# top_schem_rev10.net
KiCad netlist of a schematic drawn in Altium Designer
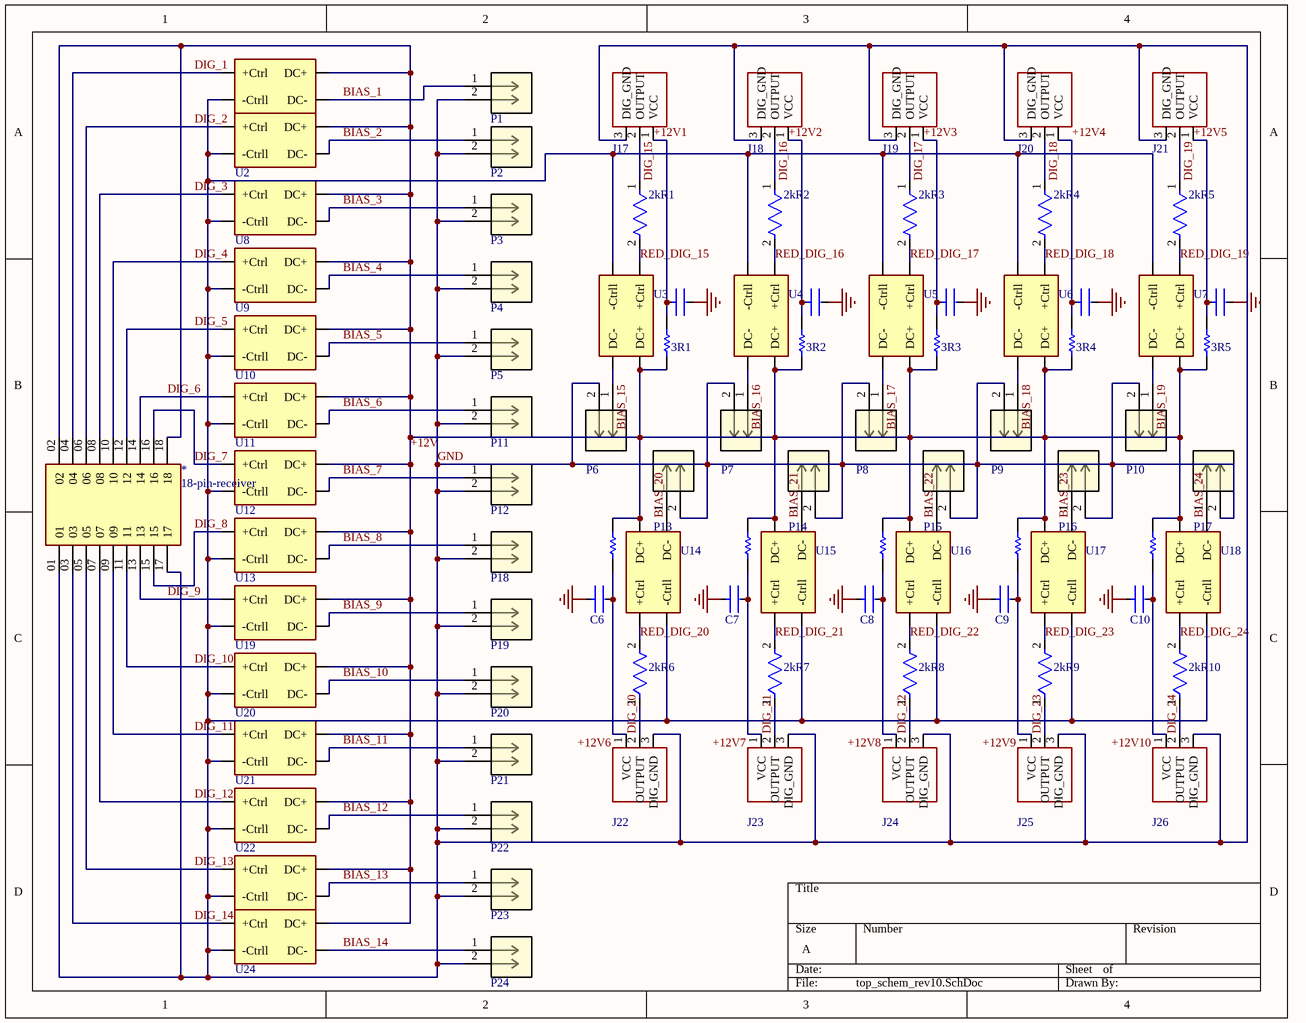
[diagram p0: top_schem_rev10.SchDoc]

(export (version "E")
  (design (tool "Eeschema 10.0.6"))
  (components
    (comp (ref "*")
      (value "18-pin-receiver")
      (footprint "18-pin-receiver")
      (libsource (lib "top_schlib") (part "18-pin-receiver"))
    )
    (comp (ref "2kR1")
      (value "CRCW06031K80FKEA")
      (footprint "2kOhm")
      (description "Res Thick Film 0603 1.8K Ohm 1% 1/10W ±100ppm/°C Molded SMD Paper T/R")
      (fields (field (name "MANUFACTURER") "Vishay") (field (name "TOLERANCE") "1%"))
      (libsource (lib "ps_schlib") (part "CRCW06031K80FKEA"))
    )
    (comp (ref "2kR2")
      (value "CRCW06031K80FKEA")
      (footprint "2kOhm")
      (description "Res Thick Film 0603 1.8K Ohm 1% 1/10W ±100ppm/°C Molded SMD Paper T/R")
      (fields (field (name "MANUFACTURER") "Vishay") (field (name "TOLERANCE") "1%"))
      (libsource (lib "ps_schlib") (part "CRCW06031K80FKEA"))
    )
    (comp (ref "2kR3")
      (value "CRCW06031K80FKEA")
      (footprint "2kOhm")
      (description "Res Thick Film 0603 1.8K Ohm 1% 1/10W ±100ppm/°C Molded SMD Paper T/R")
      (fields (field (name "MANUFACTURER") "Vishay") (field (name "TOLERANCE") "1%"))
      (libsource (lib "ps_schlib") (part "CRCW06031K80FKEA"))
    )
    (comp (ref "2kR4")
      (value "CRCW06031K80FKEA")
      (footprint "2kOhm")
      (description "Res Thick Film 0603 1.8K Ohm 1% 1/10W ±100ppm/°C Molded SMD Paper T/R")
      (fields (field (name "MANUFACTURER") "Vishay") (field (name "TOLERANCE") "1%"))
      (libsource (lib "ps_schlib") (part "CRCW06031K80FKEA"))
    )
    (comp (ref "2kR5")
      (value "CRCW06031K80FKEA")
      (footprint "2kOhm")
      (description "Res Thick Film 0603 1.8K Ohm 1% 1/10W ±100ppm/°C Molded SMD Paper T/R")
      (fields (field (name "MANUFACTURER") "Vishay") (field (name "TOLERANCE") "1%"))
      (libsource (lib "ps_schlib") (part "CRCW06031K80FKEA"))
    )
    (comp (ref "2kR6")
      (value "CRCW06031K80FKEA")
      (footprint "2kOhm")
      (description "Res Thick Film 0603 1.8K Ohm 1% 1/10W ±100ppm/°C Molded SMD Paper T/R")
      (fields (field (name "MANUFACTURER") "Vishay") (field (name "TOLERANCE") "1%"))
      (libsource (lib "ps_schlib") (part "CRCW06031K80FKEA"))
    )
    (comp (ref "2kR7")
      (value "CRCW06031K80FKEA")
      (footprint "2kOhm")
      (description "Res Thick Film 0603 1.8K Ohm 1% 1/10W ±100ppm/°C Molded SMD Paper T/R")
      (fields (field (name "MANUFACTURER") "Vishay") (field (name "TOLERANCE") "1%"))
      (libsource (lib "ps_schlib") (part "CRCW06031K80FKEA"))
    )
    (comp (ref "2kR8")
      (value "CRCW06031K80FKEA")
      (footprint "2kOhm")
      (description "Res Thick Film 0603 1.8K Ohm 1% 1/10W ±100ppm/°C Molded SMD Paper T/R")
      (fields (field (name "MANUFACTURER") "Vishay") (field (name "TOLERANCE") "1%"))
      (libsource (lib "ps_schlib") (part "CRCW06031K80FKEA"))
    )
    (comp (ref "2kR9")
      (value "CRCW06031K80FKEA")
      (footprint "2kOhm")
      (description "Res Thick Film 0603 1.8K Ohm 1% 1/10W ±100ppm/°C Molded SMD Paper T/R")
      (fields (field (name "MANUFACTURER") "Vishay") (field (name "TOLERANCE") "1%"))
      (libsource (lib "ps_schlib") (part "CRCW06031K80FKEA"))
    )
    (comp (ref "2kR10")
      (value "CRCW06031K80FKEA")
      (footprint "2kOhm")
      (description "Res Thick Film 0603 1.8K Ohm 1% 1/10W ±100ppm/°C Molded SMD Paper T/R")
      (fields (field (name "MANUFACTURER") "Vishay") (field (name "TOLERANCE") "1%"))
      (libsource (lib "ps_schlib") (part "CRCW06031K80FKEA"))
    )
    (comp (ref "3R1")
      (value "ERJ-2BQJR30X")
      (footprint "03 Ohm")
      (description "RES 0.3 OHM 5% 1/6W 0402")
      (fields (field (name "MANUFACTURER") "Panasonic") (field (name "TOLERANCE") "5%"))
      (libsource (lib "ps_schlib") (part "ERJ-2BQJR30X"))
    )
    (comp (ref "3R2")
      (value "ERJ-2BQJR30X")
      (footprint "03 Ohm")
      (description "RES 0.3 OHM 5% 1/6W 0402")
      (fields (field (name "MANUFACTURER") "Panasonic") (field (name "TOLERANCE") "5%"))
      (libsource (lib "ps_schlib") (part "ERJ-2BQJR30X"))
    )
    (comp (ref "3R3")
      (value "ERJ-2BQJR30X")
      (footprint "03 Ohm")
      (description "RES 0.3 OHM 5% 1/6W 0402")
      (fields (field (name "MANUFACTURER") "Panasonic") (field (name "TOLERANCE") "5%"))
      (libsource (lib "ps_schlib") (part "ERJ-2BQJR30X"))
    )
    (comp (ref "3R4")
      (value "ERJ-2BQJR30X")
      (footprint "03 Ohm")
      (description "RES 0.3 OHM 5% 1/6W 0402")
      (fields (field (name "MANUFACTURER") "Panasonic") (field (name "TOLERANCE") "5%"))
      (libsource (lib "ps_schlib") (part "ERJ-2BQJR30X"))
    )
    (comp (ref "3R5")
      (value "ERJ-2BQJR30X")
      (footprint "03 Ohm")
      (description "RES 0.3 OHM 5% 1/6W 0402")
      (fields (field (name "MANUFACTURER") "Panasonic") (field (name "TOLERANCE") "5%"))
      (libsource (lib "ps_schlib") (part "ERJ-2BQJR30X"))
    )
    (comp (ref "3R6")
      (value "ERJ-2BQJR30X")
      (footprint "03 Ohm")
      (description "RES 0.3 OHM 5% 1/6W 0402")
      (fields (field (name "MANUFACTURER") "Panasonic") (field (name "TOLERANCE") "5%"))
      (libsource (lib "ps_schlib") (part "ERJ-2BQJR30X"))
    )
    (comp (ref "3R7")
      (value "ERJ-2BQJR30X")
      (footprint "03 Ohm")
      (description "RES 0.3 OHM 5% 1/6W 0402")
      (fields (field (name "MANUFACTURER") "Panasonic") (field (name "TOLERANCE") "5%"))
      (libsource (lib "ps_schlib") (part "ERJ-2BQJR30X"))
    )
    (comp (ref "3R8")
      (value "ERJ-2BQJR30X")
      (footprint "03 Ohm")
      (description "RES 0.3 OHM 5% 1/6W 0402")
      (fields (field (name "MANUFACTURER") "Panasonic") (field (name "TOLERANCE") "5%"))
      (libsource (lib "ps_schlib") (part "ERJ-2BQJR30X"))
    )
    (comp (ref "3R9")
      (value "ERJ-2BQJR30X")
      (footprint "03 Ohm")
      (description "RES 0.3 OHM 5% 1/6W 0402")
      (fields (field (name "MANUFACTURER") "Panasonic") (field (name "TOLERANCE") "5%"))
      (libsource (lib "ps_schlib") (part "ERJ-2BQJR30X"))
    )
    (comp (ref "3R10")
      (value "ERJ-2BQJR30X")
      (footprint "03 Ohm")
      (description "RES 0.3 OHM 5% 1/6W 0402")
      (fields (field (name "MANUFACTURER") "Panasonic") (field (name "TOLERANCE") "5%"))
      (libsource (lib "ps_schlib") (part "ERJ-2BQJR30X"))
    )
    (comp (ref "C1")
      (value "C0805C104K5RACTU")
      (footprint "100nF")
      (description "Cap Ceramic 0.1uF 50V X7R 10% SMD 2.0 x 1.2 mm 125 C Paper T/R")
      (fields (field (name "MANUFACTURER") "KEMET") (field (name "TOLERANCE") "10%"))
      (libsource (lib "ps_schlib") (part "C0805C104K5RACTU"))
    )
    (comp (ref "C2")
      (value "C0805C104K5RACTU")
      (footprint "100nF")
      (description "Cap Ceramic 0.1uF 50V X7R 10% SMD 2.0 x 1.2 mm 125 C Paper T/R")
      (fields (field (name "MANUFACTURER") "KEMET") (field (name "TOLERANCE") "10%"))
      (libsource (lib "ps_schlib") (part "C0805C104K5RACTU"))
    )
    (comp (ref "C3")
      (value "C0805C104K5RACTU")
      (footprint "100nF")
      (description "Cap Ceramic 0.1uF 50V X7R 10% SMD 2.0 x 1.2 mm 125 C Paper T/R")
      (fields (field (name "MANUFACTURER") "KEMET") (field (name "TOLERANCE") "10%"))
      (libsource (lib "ps_schlib") (part "C0805C104K5RACTU"))
    )
    (comp (ref "C4")
      (value "C0805C104K5RACTU")
      (footprint "100nF")
      (description "Cap Ceramic 0.1uF 50V X7R 10% SMD 2.0 x 1.2 mm 125 C Paper T/R")
      (fields (field (name "MANUFACTURER") "KEMET") (field (name "TOLERANCE") "10%"))
      (libsource (lib "ps_schlib") (part "C0805C104K5RACTU"))
    )
    (comp (ref "C5")
      (value "C0805C104K5RACTU")
      (footprint "100nF")
      (description "Cap Ceramic 0.1uF 50V X7R 10% SMD 2.0 x 1.2 mm 125 C Paper T/R")
      (fields (field (name "MANUFACTURER") "KEMET") (field (name "TOLERANCE") "10%"))
      (libsource (lib "ps_schlib") (part "C0805C104K5RACTU"))
    )
    (comp (ref "C6")
      (value "C0805C104K5RACTU")
      (footprint "100nF")
      (description "Cap Ceramic 0.1uF 50V X7R 10% SMD 2.0 x 1.2 mm 125 C Paper T/R")
      (fields (field (name "MANUFACTURER") "KEMET") (field (name "TOLERANCE") "10%"))
      (libsource (lib "ps_schlib") (part "C0805C104K5RACTU"))
    )
    (comp (ref "C7")
      (value "C0805C104K5RACTU")
      (footprint "100nF")
      (description "Cap Ceramic 0.1uF 50V X7R 10% SMD 2.0 x 1.2 mm 125 C Paper T/R")
      (fields (field (name "MANUFACTURER") "KEMET") (field (name "TOLERANCE") "10%"))
      (libsource (lib "ps_schlib") (part "C0805C104K5RACTU"))
    )
    (comp (ref "C8")
      (value "C0805C104K5RACTU")
      (footprint "100nF")
      (description "Cap Ceramic 0.1uF 50V X7R 10% SMD 2.0 x 1.2 mm 125 C Paper T/R")
      (fields (field (name "MANUFACTURER") "KEMET") (field (name "TOLERANCE") "10%"))
      (libsource (lib "ps_schlib") (part "C0805C104K5RACTU"))
    )
    (comp (ref "C9")
      (value "C0805C104K5RACTU")
      (footprint "100nF")
      (description "Cap Ceramic 0.1uF 50V X7R 10% SMD 2.0 x 1.2 mm 125 C Paper T/R")
      (fields (field (name "MANUFACTURER") "KEMET") (field (name "TOLERANCE") "10%"))
      (libsource (lib "ps_schlib") (part "C0805C104K5RACTU"))
    )
    (comp (ref "C10")
      (value "C0805C104K5RACTU")
      (footprint "100nF")
      (description "Cap Ceramic 0.1uF 50V X7R 10% SMD 2.0 x 1.2 mm 125 C Paper T/R")
      (fields (field (name "MANUFACTURER") "KEMET") (field (name "TOLERANCE") "10%"))
      (libsource (lib "ps_schlib") (part "C0805C104K5RACTU"))
    )
    (comp (ref "J17")
      (value "IF-D95T")
      (footprint "IF-D95")
      (description "DETECTOR PHOTOLOGIC TTL/CMOS")
      (fields (field (name "MANUFACTURER") "Industrial Fiber Optics"))
      (libsource (lib "ps_schlib") (part "IF-D95T"))
    )
    (comp (ref "J18")
      (value "IF-D95T")
      (footprint "IF-D95")
      (description "DETECTOR PHOTOLOGIC TTL/CMOS")
      (fields (field (name "MANUFACTURER") "Industrial Fiber Optics"))
      (libsource (lib "ps_schlib") (part "IF-D95T"))
    )
    (comp (ref "J19")
      (value "IF-D95T")
      (footprint "IF-D95")
      (description "DETECTOR PHOTOLOGIC TTL/CMOS")
      (fields (field (name "MANUFACTURER") "Industrial Fiber Optics"))
      (libsource (lib "ps_schlib") (part "IF-D95T"))
    )
    (comp (ref "J20")
      (value "IF-D95T")
      (footprint "IF-D95")
      (description "DETECTOR PHOTOLOGIC TTL/CMOS")
      (fields (field (name "MANUFACTURER") "Industrial Fiber Optics"))
      (libsource (lib "ps_schlib") (part "IF-D95T"))
    )
    (comp (ref "J21")
      (value "IF-D95T")
      (footprint "IF-D95")
      (description "DETECTOR PHOTOLOGIC TTL/CMOS")
      (fields (field (name "MANUFACTURER") "Industrial Fiber Optics"))
      (libsource (lib "ps_schlib") (part "IF-D95T"))
    )
    (comp (ref "J22")
      (value "IF-D95T")
      (footprint "IF-D95")
      (description "DETECTOR PHOTOLOGIC TTL/CMOS")
      (fields (field (name "MANUFACTURER") "Industrial Fiber Optics"))
      (libsource (lib "ps_schlib") (part "IF-D95T"))
    )
    (comp (ref "J23")
      (value "IF-D95T")
      (footprint "IF-D95")
      (description "DETECTOR PHOTOLOGIC TTL/CMOS")
      (fields (field (name "MANUFACTURER") "Industrial Fiber Optics"))
      (libsource (lib "ps_schlib") (part "IF-D95T"))
    )
    (comp (ref "J24")
      (value "IF-D95T")
      (footprint "IF-D95")
      (description "DETECTOR PHOTOLOGIC TTL/CMOS")
      (fields (field (name "MANUFACTURER") "Industrial Fiber Optics"))
      (libsource (lib "ps_schlib") (part "IF-D95T"))
    )
    (comp (ref "J25")
      (value "IF-D95T")
      (footprint "IF-D95")
      (description "DETECTOR PHOTOLOGIC TTL/CMOS")
      (fields (field (name "MANUFACTURER") "Industrial Fiber Optics"))
      (libsource (lib "ps_schlib") (part "IF-D95T"))
    )
    (comp (ref "J26")
      (value "IF-D95T")
      (footprint "IF-D95")
      (description "DETECTOR PHOTOLOGIC TTL/CMOS")
      (fields (field (name "MANUFACTURER") "Industrial Fiber Optics"))
      (libsource (lib "ps_schlib") (part "IF-D95T"))
    )
    (comp (ref "P1")
      (value "1054311102")
      (footprint "CONN_1054311102_MOL")
      (fields (field (name "MANUFACTURER") "Molex"))
      (libsource (lib "ps_schlib") (part "1054311102"))
    )
    (comp (ref "P2")
      (value "1054311102")
      (footprint "CONN_1054311102_MOL")
      (fields (field (name "MANUFACTURER") "Molex"))
      (libsource (lib "ps_schlib") (part "1054311102"))
    )
    (comp (ref "P3")
      (value "1054311102")
      (footprint "CONN_1054311102_MOL")
      (fields (field (name "MANUFACTURER") "Molex"))
      (libsource (lib "ps_schlib") (part "1054311102"))
    )
    (comp (ref "P4")
      (value "1054311102")
      (footprint "CONN_1054311102_MOL")
      (fields (field (name "MANUFACTURER") "Molex"))
      (libsource (lib "ps_schlib") (part "1054311102"))
    )
    (comp (ref "P5")
      (value "1054311102")
      (footprint "CONN_1054311102_MOL")
      (fields (field (name "MANUFACTURER") "Molex"))
      (libsource (lib "ps_schlib") (part "1054311102"))
    )
    (comp (ref "P6")
      (value "1054311102")
      (footprint "CONN_1054311102_MOL")
      (fields (field (name "MANUFACTURER") "Molex"))
      (libsource (lib "") (part "1054311102_2"))
    )
    (comp (ref "P7")
      (value "1054311102")
      (footprint "CONN_1054311102_MOL")
      (fields (field (name "MANUFACTURER") "Molex"))
      (libsource (lib "") (part "1054311102_2"))
    )
    (comp (ref "P8")
      (value "1054311102")
      (footprint "CONN_1054311102_MOL")
      (fields (field (name "MANUFACTURER") "Molex"))
      (libsource (lib "") (part "1054311102_2"))
    )
    (comp (ref "P9")
      (value "1054311102")
      (footprint "CONN_1054311102_MOL")
      (fields (field (name "MANUFACTURER") "Molex"))
      (libsource (lib "") (part "1054311102_2"))
    )
    (comp (ref "P10")
      (value "1054311102")
      (footprint "CONN_1054311102_MOL")
      (fields (field (name "MANUFACTURER") "Molex"))
      (libsource (lib "") (part "1054311102_2"))
    )
    (comp (ref "P11")
      (value "1054311102")
      (footprint "CONN_1054311102_MOL")
      (fields (field (name "MANUFACTURER") "Molex"))
      (libsource (lib "ps_schlib") (part "1054311102"))
    )
    (comp (ref "P12")
      (value "1054311102")
      (footprint "CONN_1054311102_MOL")
      (fields (field (name "MANUFACTURER") "Molex"))
      (libsource (lib "ps_schlib") (part "1054311102"))
    )
    (comp (ref "P13")
      (value "1054311102")
      (footprint "CONN_1054311102_MOL")
      (fields (field (name "MANUFACTURER") "Molex"))
      (libsource (lib "") (part "1054311102_1"))
    )
    (comp (ref "P14")
      (value "1054311102")
      (footprint "CONN_1054311102_MOL")
      (fields (field (name "MANUFACTURER") "Molex"))
      (libsource (lib "") (part "1054311102_1"))
    )
    (comp (ref "P15")
      (value "1054311102")
      (footprint "CONN_1054311102_MOL")
      (fields (field (name "MANUFACTURER") "Molex"))
      (libsource (lib "") (part "1054311102_1"))
    )
    (comp (ref "P16")
      (value "1054311102")
      (footprint "CONN_1054311102_MOL")
      (fields (field (name "MANUFACTURER") "Molex"))
      (libsource (lib "") (part "1054311102_1"))
    )
    (comp (ref "P17")
      (value "1054311102")
      (footprint "CONN_1054311102_MOL")
      (fields (field (name "MANUFACTURER") "Molex"))
      (libsource (lib "") (part "1054311102_1"))
    )
    (comp (ref "P18")
      (value "1054311102")
      (footprint "CONN_1054311102_MOL")
      (fields (field (name "MANUFACTURER") "Molex"))
      (libsource (lib "ps_schlib") (part "1054311102"))
    )
    (comp (ref "P19")
      (value "1054311102")
      (footprint "CONN_1054311102_MOL")
      (fields (field (name "MANUFACTURER") "Molex"))
      (libsource (lib "ps_schlib") (part "1054311102"))
    )
    (comp (ref "P20")
      (value "1054311102")
      (footprint "CONN_1054311102_MOL")
      (fields (field (name "MANUFACTURER") "Molex"))
      (libsource (lib "ps_schlib") (part "1054311102"))
    )
    (comp (ref "P21")
      (value "1054311102")
      (footprint "CONN_1054311102_MOL")
      (fields (field (name "MANUFACTURER") "Molex"))
      (libsource (lib "ps_schlib") (part "1054311102"))
    )
    (comp (ref "P22")
      (value "1054311102")
      (footprint "CONN_1054311102_MOL")
      (fields (field (name "MANUFACTURER") "Molex"))
      (libsource (lib "ps_schlib") (part "1054311102"))
    )
    (comp (ref "P23")
      (value "1054311102")
      (footprint "CONN_1054311102_MOL")
      (fields (field (name "MANUFACTURER") "Molex"))
      (libsource (lib "ps_schlib") (part "1054311102"))
    )
    (comp (ref "P24")
      (value "1054311102")
      (footprint "CONN_1054311102_MOL")
      (fields (field (name "MANUFACTURER") "Molex"))
      (libsource (lib "ps_schlib") (part "1054311102"))
    )
    (comp (ref "U1")
      (value "Solid state relay")
      (footprint "CPC1002N")
      (libsource (lib "ps_schlib") (part "CPC1002N"))
    )
    (comp (ref "U2")
      (value "Solid state relay")
      (footprint "CPC1002N")
      (libsource (lib "ps_schlib") (part "CPC1002N"))
    )
    (comp (ref "U3")
      (value "Solid state relay")
      (footprint "CPC1002N")
      (libsource (lib "") (part "CPC1002N_1"))
    )
    (comp (ref "U4")
      (value "Solid state relay")
      (footprint "CPC1002N")
      (libsource (lib "") (part "CPC1002N_1"))
    )
    (comp (ref "U5")
      (value "Solid state relay")
      (footprint "CPC1002N")
      (libsource (lib "") (part "CPC1002N_1"))
    )
    (comp (ref "U6")
      (value "Solid state relay")
      (footprint "CPC1002N")
      (libsource (lib "") (part "CPC1002N_1"))
    )
    (comp (ref "U7")
      (value "Solid state relay")
      (footprint "CPC1002N")
      (libsource (lib "") (part "CPC1002N_1"))
    )
    (comp (ref "U8")
      (value "Solid state relay")
      (footprint "CPC1002N")
      (libsource (lib "ps_schlib") (part "CPC1002N"))
    )
    (comp (ref "U9")
      (value "Solid state relay")
      (footprint "CPC1002N")
      (libsource (lib "ps_schlib") (part "CPC1002N"))
    )
    (comp (ref "U10")
      (value "Solid state relay")
      (footprint "CPC1002N")
      (libsource (lib "ps_schlib") (part "CPC1002N"))
    )
    (comp (ref "U11")
      (value "Solid state relay")
      (footprint "CPC1002N")
      (libsource (lib "ps_schlib") (part "CPC1002N"))
    )
    (comp (ref "U12")
      (value "Solid state relay")
      (footprint "CPC1002N")
      (libsource (lib "ps_schlib") (part "CPC1002N"))
    )
    (comp (ref "U13")
      (value "Solid state relay")
      (footprint "CPC1002N")
      (libsource (lib "ps_schlib") (part "CPC1002N"))
    )
    (comp (ref "U14")
      (value "Solid state relay")
      (footprint "CPC1002N")
      (libsource (lib "") (part "CPC1002N_2"))
    )
    (comp (ref "U15")
      (value "Solid state relay")
      (footprint "CPC1002N")
      (libsource (lib "") (part "CPC1002N_2"))
    )
    (comp (ref "U16")
      (value "Solid state relay")
      (footprint "CPC1002N")
      (libsource (lib "") (part "CPC1002N_2"))
    )
    (comp (ref "U17")
      (value "Solid state relay")
      (footprint "CPC1002N")
      (libsource (lib "") (part "CPC1002N_2"))
    )
    (comp (ref "U18")
      (value "Solid state relay")
      (footprint "CPC1002N")
      (libsource (lib "") (part "CPC1002N_2"))
    )
    (comp (ref "U19")
      (value "Solid state relay")
      (footprint "CPC1002N")
      (libsource (lib "ps_schlib") (part "CPC1002N"))
    )
    (comp (ref "U20")
      (value "Solid state relay")
      (footprint "CPC1002N")
      (libsource (lib "ps_schlib") (part "CPC1002N"))
    )
    (comp (ref "U21")
      (value "Solid state relay")
      (footprint "CPC1002N")
      (libsource (lib "ps_schlib") (part "CPC1002N"))
    )
    (comp (ref "U22")
      (value "Solid state relay")
      (footprint "CPC1002N")
      (libsource (lib "ps_schlib") (part "CPC1002N"))
    )
    (comp (ref "U23")
      (value "Solid state relay")
      (footprint "CPC1002N")
      (libsource (lib "ps_schlib") (part "CPC1002N"))
    )
    (comp (ref "U24")
      (value "Solid state relay")
      (footprint "CPC1002N")
      (libsource (lib "ps_schlib") (part "CPC1002N"))
    )
  )
  (nets
    (net (code "1") (name "/+12V") (class "Default")
      (node (ref "*") (pin "02") (pinfunction "02_02") (pintype "passive"))
      (node (ref "*") (pin "18") (pinfunction "18_18") (pintype "passive"))
      (node (ref "3R1") (pin "1") (pinfunction "1_1") (pintype "passive"))
      (node (ref "3R10") (pin "2") (pinfunction "2_2") (pintype "passive"))
      (node (ref "3R2") (pin "1") (pinfunction "1_1") (pintype "passive"))
      (node (ref "3R3") (pin "1") (pinfunction "1_1") (pintype "passive"))
      (node (ref "3R4") (pin "1") (pinfunction "1_1") (pintype "passive"))
      (node (ref "3R5") (pin "1") (pinfunction "1_1") (pintype "passive"))
      (node (ref "3R6") (pin "2") (pinfunction "2_2") (pintype "passive"))
      (node (ref "3R7") (pin "2") (pinfunction "2_2") (pintype "passive"))
      (node (ref "3R8") (pin "2") (pinfunction "2_2") (pintype "passive"))
      (node (ref "3R9") (pin "2") (pinfunction "2_2") (pintype "passive"))
      (node (ref "U1") (pin "4") (pinfunction "DC+_4") (pintype "passive"))
      (node (ref "U10") (pin "4") (pinfunction "DC+_4") (pintype "passive"))
      (node (ref "U11") (pin "4") (pinfunction "DC+_4") (pintype "passive"))
      (node (ref "U12") (pin "4") (pinfunction "DC+_4") (pintype "passive"))
      (node (ref "U13") (pin "4") (pinfunction "DC+_4") (pintype "passive"))
      (node (ref "U14") (pin "4") (pinfunction "DC+_4") (pintype "passive"))
      (node (ref "U15") (pin "4") (pinfunction "DC+_4") (pintype "passive"))
      (node (ref "U16") (pin "4") (pinfunction "DC+_4") (pintype "passive"))
      (node (ref "U17") (pin "4") (pinfunction "DC+_4") (pintype "passive"))
      (node (ref "U18") (pin "4") (pinfunction "DC+_4") (pintype "passive"))
      (node (ref "U19") (pin "4") (pinfunction "DC+_4") (pintype "passive"))
      (node (ref "U2") (pin "4") (pinfunction "DC+_4") (pintype "passive"))
      (node (ref "U20") (pin "4") (pinfunction "DC+_4") (pintype "passive"))
      (node (ref "U21") (pin "4") (pinfunction "DC+_4") (pintype "passive"))
      (node (ref "U22") (pin "4") (pinfunction "DC+_4") (pintype "passive"))
      (node (ref "U23") (pin "4") (pinfunction "DC+_4") (pintype "passive"))
      (node (ref "U24") (pin "4") (pinfunction "DC+_4") (pintype "passive"))
      (node (ref "U3") (pin "4") (pinfunction "DC+_4") (pintype "passive"))
      (node (ref "U4") (pin "4") (pinfunction "DC+_4") (pintype "passive"))
      (node (ref "U5") (pin "4") (pinfunction "DC+_4") (pintype "passive"))
      (node (ref "U6") (pin "4") (pinfunction "DC+_4") (pintype "passive"))
      (node (ref "U7") (pin "4") (pinfunction "DC+_4") (pintype "passive"))
      (node (ref "U8") (pin "4") (pinfunction "DC+_4") (pintype "passive"))
      (node (ref "U9") (pin "4") (pinfunction "DC+_4") (pintype "passive"))
    )
    (net (code "2") (name "/+12V1") (class "Default")
      (node (ref "3R1") (pin "2") (pinfunction "2_2") (pintype "passive"))
      (node (ref "C1") (pin "1") (pinfunction "1_1") (pintype "passive"))
      (node (ref "J17") (pin "1") (pinfunction "VCC_1") (pintype "passive"))
    )
    (net (code "3") (name "/+12V2") (class "Default")
      (node (ref "3R2") (pin "2") (pinfunction "2_2") (pintype "passive"))
      (node (ref "C2") (pin "1") (pinfunction "1_1") (pintype "passive"))
      (node (ref "J18") (pin "1") (pinfunction "VCC_1") (pintype "passive"))
    )
    (net (code "4") (name "/+12V3") (class "Default")
      (node (ref "3R3") (pin "2") (pinfunction "2_2") (pintype "passive"))
      (node (ref "C3") (pin "1") (pinfunction "1_1") (pintype "passive"))
      (node (ref "J19") (pin "1") (pinfunction "VCC_1") (pintype "passive"))
    )
    (net (code "5") (name "/+12V4") (class "Default")
      (node (ref "3R4") (pin "2") (pinfunction "2_2") (pintype "passive"))
      (node (ref "C4") (pin "1") (pinfunction "1_1") (pintype "passive"))
      (node (ref "J20") (pin "1") (pinfunction "VCC_1") (pintype "passive"))
    )
    (net (code "6") (name "/+12V5") (class "Default")
      (node (ref "3R5") (pin "2") (pinfunction "2_2") (pintype "passive"))
      (node (ref "C5") (pin "1") (pinfunction "1_1") (pintype "passive"))
      (node (ref "J21") (pin "1") (pinfunction "VCC_1") (pintype "passive"))
    )
    (net (code "7") (name "/+12V6") (class "Default")
      (node (ref "3R6") (pin "1") (pinfunction "1_1") (pintype "passive"))
      (node (ref "C6") (pin "2") (pinfunction "2_2") (pintype "passive"))
      (node (ref "J22") (pin "1") (pinfunction "VCC_1") (pintype "passive"))
    )
    (net (code "8") (name "/+12V7") (class "Default")
      (node (ref "3R7") (pin "1") (pinfunction "1_1") (pintype "passive"))
      (node (ref "C7") (pin "2") (pinfunction "2_2") (pintype "passive"))
      (node (ref "J23") (pin "1") (pinfunction "VCC_1") (pintype "passive"))
    )
    (net (code "9") (name "/+12V8") (class "Default")
      (node (ref "3R8") (pin "1") (pinfunction "1_1") (pintype "passive"))
      (node (ref "C8") (pin "2") (pinfunction "2_2") (pintype "passive"))
      (node (ref "J24") (pin "1") (pinfunction "VCC_1") (pintype "passive"))
    )
    (net (code "10") (name "/+12V9") (class "Default")
      (node (ref "3R9") (pin "1") (pinfunction "1_1") (pintype "passive"))
      (node (ref "C9") (pin "2") (pinfunction "2_2") (pintype "passive"))
      (node (ref "J25") (pin "1") (pinfunction "VCC_1") (pintype "passive"))
    )
    (net (code "11") (name "/+12V10") (class "Default")
      (node (ref "3R10") (pin "1") (pinfunction "1_1") (pintype "passive"))
      (node (ref "C10") (pin "2") (pinfunction "2_2") (pintype "passive"))
      (node (ref "J26") (pin "1") (pinfunction "VCC_1") (pintype "passive"))
    )
    (net (code "12") (name "/BIAS_1") (class "Default")
      (node (ref "P1") (pin "1") (pinfunction "1_1") (pintype "passive"))
      (node (ref "U1") (pin "3") (pinfunction "DC-_3") (pintype "passive"))
    )
    (net (code "13") (name "/BIAS_2") (class "Default")
      (node (ref "P2") (pin "1") (pinfunction "1_1") (pintype "passive"))
      (node (ref "U2") (pin "3") (pinfunction "DC-_3") (pintype "passive"))
    )
    (net (code "14") (name "/BIAS_3") (class "Default")
      (node (ref "P3") (pin "1") (pinfunction "1_1") (pintype "passive"))
      (node (ref "U8") (pin "3") (pinfunction "DC-_3") (pintype "passive"))
    )
    (net (code "15") (name "/BIAS_4") (class "Default")
      (node (ref "P4") (pin "1") (pinfunction "1_1") (pintype "passive"))
      (node (ref "U9") (pin "3") (pinfunction "DC-_3") (pintype "passive"))
    )
    (net (code "16") (name "/BIAS_5") (class "Default")
      (node (ref "P5") (pin "1") (pinfunction "1_1") (pintype "passive"))
      (node (ref "U10") (pin "3") (pinfunction "DC-_3") (pintype "passive"))
    )
    (net (code "17") (name "/BIAS_6") (class "Default")
      (node (ref "P11") (pin "1") (pinfunction "1_1") (pintype "passive"))
      (node (ref "U11") (pin "3") (pinfunction "DC-_3") (pintype "passive"))
    )
    (net (code "18") (name "/BIAS_7") (class "Default")
      (node (ref "P12") (pin "1") (pinfunction "1_1") (pintype "passive"))
      (node (ref "U12") (pin "3") (pinfunction "DC-_3") (pintype "passive"))
    )
    (net (code "19") (name "/BIAS_8") (class "Default")
      (node (ref "P18") (pin "1") (pinfunction "1_1") (pintype "passive"))
      (node (ref "U13") (pin "3") (pinfunction "DC-_3") (pintype "passive"))
    )
    (net (code "20") (name "/BIAS_9") (class "Default")
      (node (ref "P19") (pin "1") (pinfunction "1_1") (pintype "passive"))
      (node (ref "U19") (pin "3") (pinfunction "DC-_3") (pintype "passive"))
    )
    (net (code "21") (name "/BIAS_10") (class "Default")
      (node (ref "P20") (pin "1") (pinfunction "1_1") (pintype "passive"))
      (node (ref "U20") (pin "3") (pinfunction "DC-_3") (pintype "passive"))
    )
    (net (code "22") (name "/BIAS_11") (class "Default")
      (node (ref "P21") (pin "1") (pinfunction "1_1") (pintype "passive"))
      (node (ref "U21") (pin "3") (pinfunction "DC-_3") (pintype "passive"))
    )
    (net (code "23") (name "/BIAS_12") (class "Default")
      (node (ref "P22") (pin "1") (pinfunction "1_1") (pintype "passive"))
      (node (ref "U22") (pin "3") (pinfunction "DC-_3") (pintype "passive"))
    )
    (net (code "24") (name "/BIAS_13") (class "Default")
      (node (ref "P23") (pin "1") (pinfunction "1_1") (pintype "passive"))
      (node (ref "U23") (pin "3") (pinfunction "DC-_3") (pintype "passive"))
    )
    (net (code "25") (name "/BIAS_14") (class "Default")
      (node (ref "P24") (pin "1") (pinfunction "1_1") (pintype "passive"))
      (node (ref "U24") (pin "3") (pinfunction "DC-_3") (pintype "passive"))
    )
    (net (code "26") (name "/BIAS_15") (class "Default")
      (node (ref "P6") (pin "1") (pinfunction "1_1") (pintype "passive"))
      (node (ref "U3") (pin "3") (pinfunction "DC-_3") (pintype "passive"))
    )
    (net (code "27") (name "/BIAS_16") (class "Default")
      (node (ref "P7") (pin "1") (pinfunction "1_1") (pintype "passive"))
      (node (ref "U4") (pin "3") (pinfunction "DC-_3") (pintype "passive"))
    )
    (net (code "28") (name "/BIAS_17") (class "Default")
      (node (ref "P8") (pin "1") (pinfunction "1_1") (pintype "passive"))
      (node (ref "U5") (pin "3") (pinfunction "DC-_3") (pintype "passive"))
    )
    (net (code "29") (name "/BIAS_18") (class "Default")
      (node (ref "P9") (pin "1") (pinfunction "1_1") (pintype "passive"))
      (node (ref "U6") (pin "3") (pinfunction "DC-_3") (pintype "passive"))
    )
    (net (code "30") (name "/BIAS_19") (class "Default")
      (node (ref "P10") (pin "1") (pinfunction "1_1") (pintype "passive"))
      (node (ref "U7") (pin "3") (pinfunction "DC-_3") (pintype "passive"))
    )
    (net (code "31") (name "/BIAS_20") (class "Default")
      (node (ref "P13") (pin "1") (pinfunction "1_1") (pintype "passive"))
      (node (ref "U14") (pin "3") (pinfunction "DC-_3") (pintype "passive"))
    )
    (net (code "32") (name "/BIAS_21") (class "Default")
      (node (ref "P14") (pin "1") (pinfunction "1_1") (pintype "passive"))
      (node (ref "U15") (pin "3") (pinfunction "DC-_3") (pintype "passive"))
    )
    (net (code "33") (name "/BIAS_22") (class "Default")
      (node (ref "P15") (pin "1") (pinfunction "1_1") (pintype "passive"))
      (node (ref "U16") (pin "3") (pinfunction "DC-_3") (pintype "passive"))
    )
    (net (code "34") (name "/BIAS_23") (class "Default")
      (node (ref "P16") (pin "1") (pinfunction "1_1") (pintype "passive"))
      (node (ref "U17") (pin "3") (pinfunction "DC-_3") (pintype "passive"))
    )
    (net (code "35") (name "/BIAS_24") (class "Default")
      (node (ref "P17") (pin "1") (pinfunction "1_1") (pintype "passive"))
      (node (ref "U18") (pin "3") (pinfunction "DC-_3") (pintype "passive"))
    )
    (net (code "36") (name "/DIG_1") (class "Default")
      (node (ref "*") (pin "04") (pinfunction "04_04") (pintype "passive"))
      (node (ref "U1") (pin "1") (pinfunction "+Ctrl_1") (pintype "passive"))
    )
    (net (code "37") (name "/DIG_2") (class "Default")
      (node (ref "*") (pin "06") (pinfunction "06_06") (pintype "passive"))
      (node (ref "U2") (pin "1") (pinfunction "+Ctrl_1") (pintype "passive"))
    )
    (net (code "38") (name "/DIG_3") (class "Default")
      (node (ref "*") (pin "08") (pinfunction "08_08") (pintype "passive"))
      (node (ref "U8") (pin "1") (pinfunction "+Ctrl_1") (pintype "passive"))
    )
    (net (code "39") (name "/DIG_4") (class "Default")
      (node (ref "*") (pin "10") (pinfunction "10_10") (pintype "passive"))
      (node (ref "U9") (pin "1") (pinfunction "+Ctrl_1") (pintype "passive"))
    )
    (net (code "40") (name "/DIG_5") (class "Default")
      (node (ref "*") (pin "12") (pinfunction "12_12") (pintype "passive"))
      (node (ref "U10") (pin "1") (pinfunction "+Ctrl_1") (pintype "passive"))
    )
    (net (code "41") (name "/DIG_6") (class "Default")
      (node (ref "*") (pin "14") (pinfunction "14_14") (pintype "passive"))
      (node (ref "U11") (pin "1") (pinfunction "+Ctrl_1") (pintype "passive"))
    )
    (net (code "42") (name "/DIG_7") (class "Default")
      (node (ref "*") (pin "16") (pinfunction "16_16") (pintype "passive"))
      (node (ref "U12") (pin "1") (pinfunction "+Ctrl_1") (pintype "passive"))
    )
    (net (code "43") (name "/DIG_8") (class "Default")
      (node (ref "*") (pin "15") (pinfunction "15_15") (pintype "passive"))
      (node (ref "U13") (pin "1") (pinfunction "+Ctrl_1") (pintype "passive"))
    )
    (net (code "44") (name "/DIG_9") (class "Default")
      (node (ref "*") (pin "13") (pinfunction "13_13") (pintype "passive"))
      (node (ref "U19") (pin "1") (pinfunction "+Ctrl_1") (pintype "passive"))
    )
    (net (code "45") (name "/DIG_10") (class "Default")
      (node (ref "*") (pin "11") (pinfunction "11_11") (pintype "passive"))
      (node (ref "U20") (pin "1") (pinfunction "+Ctrl_1") (pintype "passive"))
    )
    (net (code "46") (name "/DIG_11") (class "Default")
      (node (ref "*") (pin "09") (pinfunction "09_09") (pintype "passive"))
      (node (ref "U21") (pin "1") (pinfunction "+Ctrl_1") (pintype "passive"))
    )
    (net (code "47") (name "/DIG_12") (class "Default")
      (node (ref "*") (pin "07") (pinfunction "07_07") (pintype "passive"))
      (node (ref "U22") (pin "1") (pinfunction "+Ctrl_1") (pintype "passive"))
    )
    (net (code "48") (name "/DIG_13") (class "Default")
      (node (ref "*") (pin "05") (pinfunction "05_05") (pintype "passive"))
      (node (ref "U23") (pin "1") (pinfunction "+Ctrl_1") (pintype "passive"))
    )
    (net (code "49") (name "/DIG_14") (class "Default")
      (node (ref "*") (pin "03") (pinfunction "03_03") (pintype "passive"))
      (node (ref "U24") (pin "1") (pinfunction "+Ctrl_1") (pintype "passive"))
    )
    (net (code "50") (name "/DIG_15") (class "Default")
      (node (ref "2kR1") (pin "1") (pinfunction "1_1") (pintype "passive"))
      (node (ref "J17") (pin "2") (pinfunction "OUTPUT_2") (pintype "passive"))
    )
    (net (code "51") (name "/DIG_16") (class "Default")
      (node (ref "2kR2") (pin "1") (pinfunction "1_1") (pintype "passive"))
      (node (ref "J18") (pin "2") (pinfunction "OUTPUT_2") (pintype "passive"))
    )
    (net (code "52") (name "/DIG_17") (class "Default")
      (node (ref "2kR3") (pin "1") (pinfunction "1_1") (pintype "passive"))
      (node (ref "J19") (pin "2") (pinfunction "OUTPUT_2") (pintype "passive"))
    )
    (net (code "53") (name "/DIG_18") (class "Default")
      (node (ref "2kR4") (pin "1") (pinfunction "1_1") (pintype "passive"))
      (node (ref "J20") (pin "2") (pinfunction "OUTPUT_2") (pintype "passive"))
    )
    (net (code "54") (name "/DIG_19") (class "Default")
      (node (ref "2kR5") (pin "1") (pinfunction "1_1") (pintype "passive"))
      (node (ref "J21") (pin "2") (pinfunction "OUTPUT_2") (pintype "passive"))
    )
    (net (code "55") (name "/DIG_20") (class "Default")
      (node (ref "2kR6") (pin "1") (pinfunction "1_1") (pintype "passive"))
      (node (ref "J22") (pin "2") (pinfunction "OUTPUT_2") (pintype "passive"))
    )
    (net (code "56") (name "/DIG_21") (class "Default")
      (node (ref "2kR7") (pin "1") (pinfunction "1_1") (pintype "passive"))
      (node (ref "J23") (pin "2") (pinfunction "OUTPUT_2") (pintype "passive"))
    )
    (net (code "57") (name "/DIG_22") (class "Default")
      (node (ref "2kR8") (pin "1") (pinfunction "1_1") (pintype "passive"))
      (node (ref "J24") (pin "2") (pinfunction "OUTPUT_2") (pintype "passive"))
    )
    (net (code "58") (name "/DIG_23") (class "Default")
      (node (ref "2kR9") (pin "1") (pinfunction "1_1") (pintype "passive"))
      (node (ref "J25") (pin "2") (pinfunction "OUTPUT_2") (pintype "passive"))
    )
    (net (code "59") (name "/DIG_24") (class "Default")
      (node (ref "2kR10") (pin "1") (pinfunction "1_1") (pintype "passive"))
      (node (ref "J26") (pin "2") (pinfunction "OUTPUT_2") (pintype "passive"))
    )
    (net (code "60") (name "/RED_DIG_15") (class "Default")
      (node (ref "2kR1") (pin "2") (pinfunction "2_2") (pintype "passive"))
      (node (ref "U3") (pin "1") (pinfunction "+Ctrl_1") (pintype "passive"))
    )
    (net (code "61") (name "/RED_DIG_16") (class "Default")
      (node (ref "2kR2") (pin "2") (pinfunction "2_2") (pintype "passive"))
      (node (ref "U4") (pin "1") (pinfunction "+Ctrl_1") (pintype "passive"))
    )
    (net (code "62") (name "/RED_DIG_17") (class "Default")
      (node (ref "2kR3") (pin "2") (pinfunction "2_2") (pintype "passive"))
      (node (ref "U5") (pin "1") (pinfunction "+Ctrl_1") (pintype "passive"))
    )
    (net (code "63") (name "/RED_DIG_18") (class "Default")
      (node (ref "2kR4") (pin "2") (pinfunction "2_2") (pintype "passive"))
      (node (ref "U6") (pin "1") (pinfunction "+Ctrl_1") (pintype "passive"))
    )
    (net (code "64") (name "/RED_DIG_19") (class "Default")
      (node (ref "2kR5") (pin "2") (pinfunction "2_2") (pintype "passive"))
      (node (ref "U7") (pin "1") (pinfunction "+Ctrl_1") (pintype "passive"))
    )
    (net (code "65") (name "/RED_DIG_20") (class "Default")
      (node (ref "2kR6") (pin "2") (pinfunction "2_2") (pintype "passive"))
      (node (ref "U14") (pin "1") (pinfunction "+Ctrl_1") (pintype "passive"))
    )
    (net (code "66") (name "/RED_DIG_21") (class "Default")
      (node (ref "2kR7") (pin "2") (pinfunction "2_2") (pintype "passive"))
      (node (ref "U15") (pin "1") (pinfunction "+Ctrl_1") (pintype "passive"))
    )
    (net (code "67") (name "/RED_DIG_22") (class "Default")
      (node (ref "2kR8") (pin "2") (pinfunction "2_2") (pintype "passive"))
      (node (ref "U16") (pin "1") (pinfunction "+Ctrl_1") (pintype "passive"))
    )
    (net (code "68") (name "/RED_DIG_23") (class "Default")
      (node (ref "2kR9") (pin "2") (pinfunction "2_2") (pintype "passive"))
      (node (ref "U17") (pin "1") (pinfunction "+Ctrl_1") (pintype "passive"))
    )
    (net (code "69") (name "/RED_DIG_24") (class "Default")
      (node (ref "2kR10") (pin "2") (pinfunction "2_2") (pintype "passive"))
      (node (ref "U18") (pin "1") (pinfunction "+Ctrl_1") (pintype "passive"))
    )
    (net (code "70") (name "GND") (class "Default")
      (node (ref "*") (pin "01") (pinfunction "01_01") (pintype "passive"))
      (node (ref "*") (pin "17") (pinfunction "17_17") (pintype "passive"))
      (node (ref "C1") (pin "2") (pinfunction "2_2") (pintype "passive"))
      (node (ref "C10") (pin "1") (pinfunction "1_1") (pintype "passive"))
      (node (ref "C2") (pin "2") (pinfunction "2_2") (pintype "passive"))
      (node (ref "C3") (pin "2") (pinfunction "2_2") (pintype "passive"))
      (node (ref "C4") (pin "2") (pinfunction "2_2") (pintype "passive"))
      (node (ref "C5") (pin "2") (pinfunction "2_2") (pintype "passive"))
      (node (ref "C6") (pin "1") (pinfunction "1_1") (pintype "passive"))
      (node (ref "C7") (pin "1") (pinfunction "1_1") (pintype "passive"))
      (node (ref "C8") (pin "1") (pinfunction "1_1") (pintype "passive"))
      (node (ref "C9") (pin "1") (pinfunction "1_1") (pintype "passive"))
      (node (ref "J17") (pin "3") (pinfunction "DIG_GND_3") (pintype "passive"))
      (node (ref "J18") (pin "3") (pinfunction "DIG_GND_3") (pintype "passive"))
      (node (ref "J19") (pin "3") (pinfunction "DIG_GND_3") (pintype "passive"))
      (node (ref "J20") (pin "3") (pinfunction "DIG_GND_3") (pintype "passive"))
      (node (ref "J21") (pin "3") (pinfunction "DIG_GND_3") (pintype "passive"))
      (node (ref "J22") (pin "3") (pinfunction "DIG_GND_3") (pintype "passive"))
      (node (ref "J23") (pin "3") (pinfunction "DIG_GND_3") (pintype "passive"))
      (node (ref "J24") (pin "3") (pinfunction "DIG_GND_3") (pintype "passive"))
      (node (ref "J25") (pin "3") (pinfunction "DIG_GND_3") (pintype "passive"))
      (node (ref "J26") (pin "3") (pinfunction "DIG_GND_3") (pintype "passive"))
      (node (ref "P1") (pin "2") (pinfunction "2_2") (pintype "passive"))
      (node (ref "P10") (pin "2") (pinfunction "2_2") (pintype "passive"))
      (node (ref "P11") (pin "2") (pinfunction "2_2") (pintype "passive"))
      (node (ref "P12") (pin "2") (pinfunction "2_2") (pintype "passive"))
      (node (ref "P13") (pin "2") (pinfunction "2_2") (pintype "passive"))
      (node (ref "P14") (pin "2") (pinfunction "2_2") (pintype "passive"))
      (node (ref "P15") (pin "2") (pinfunction "2_2") (pintype "passive"))
      (node (ref "P16") (pin "2") (pinfunction "2_2") (pintype "passive"))
      (node (ref "P17") (pin "2") (pinfunction "2_2") (pintype "passive"))
      (node (ref "P18") (pin "2") (pinfunction "2_2") (pintype "passive"))
      (node (ref "P19") (pin "2") (pinfunction "2_2") (pintype "passive"))
      (node (ref "P2") (pin "2") (pinfunction "2_2") (pintype "passive"))
      (node (ref "P20") (pin "2") (pinfunction "2_2") (pintype "passive"))
      (node (ref "P21") (pin "2") (pinfunction "2_2") (pintype "passive"))
      (node (ref "P22") (pin "2") (pinfunction "2_2") (pintype "passive"))
      (node (ref "P23") (pin "2") (pinfunction "2_2") (pintype "passive"))
      (node (ref "P24") (pin "2") (pinfunction "2_2") (pintype "passive"))
      (node (ref "P3") (pin "2") (pinfunction "2_2") (pintype "passive"))
      (node (ref "P4") (pin "2") (pinfunction "2_2") (pintype "passive"))
      (node (ref "P5") (pin "2") (pinfunction "2_2") (pintype "passive"))
      (node (ref "P6") (pin "2") (pinfunction "2_2") (pintype "passive"))
      (node (ref "P7") (pin "2") (pinfunction "2_2") (pintype "passive"))
      (node (ref "P8") (pin "2") (pinfunction "2_2") (pintype "passive"))
      (node (ref "P9") (pin "2") (pinfunction "2_2") (pintype "passive"))
      (node (ref "U1") (pin "2") (pinfunction "-Ctrll_2") (pintype "passive"))
      (node (ref "U10") (pin "2") (pinfunction "-Ctrll_2") (pintype "passive"))
      (node (ref "U11") (pin "2") (pinfunction "-Ctrll_2") (pintype "passive"))
      (node (ref "U12") (pin "2") (pinfunction "-Ctrll_2") (pintype "passive"))
      (node (ref "U13") (pin "2") (pinfunction "-Ctrll_2") (pintype "passive"))
      (node (ref "U14") (pin "2") (pinfunction "-Ctrll_2") (pintype "passive"))
      (node (ref "U15") (pin "2") (pinfunction "-Ctrll_2") (pintype "passive"))
      (node (ref "U16") (pin "2") (pinfunction "-Ctrll_2") (pintype "passive"))
      (node (ref "U17") (pin "2") (pinfunction "-Ctrll_2") (pintype "passive"))
      (node (ref "U18") (pin "2") (pinfunction "-Ctrll_2") (pintype "passive"))
      (node (ref "U19") (pin "2") (pinfunction "-Ctrll_2") (pintype "passive"))
      (node (ref "U2") (pin "2") (pinfunction "-Ctrll_2") (pintype "passive"))
      (node (ref "U20") (pin "2") (pinfunction "-Ctrll_2") (pintype "passive"))
      (node (ref "U21") (pin "2") (pinfunction "-Ctrll_2") (pintype "passive"))
      (node (ref "U22") (pin "2") (pinfunction "-Ctrll_2") (pintype "passive"))
      (node (ref "U23") (pin "2") (pinfunction "-Ctrll_2") (pintype "passive"))
      (node (ref "U24") (pin "2") (pinfunction "-Ctrll_2") (pintype "passive"))
      (node (ref "U3") (pin "2") (pinfunction "-Ctrll_2") (pintype "passive"))
      (node (ref "U4") (pin "2") (pinfunction "-Ctrll_2") (pintype "passive"))
      (node (ref "U5") (pin "2") (pinfunction "-Ctrll_2") (pintype "passive"))
      (node (ref "U6") (pin "2") (pinfunction "-Ctrll_2") (pintype "passive"))
      (node (ref "U7") (pin "2") (pinfunction "-Ctrll_2") (pintype "passive"))
      (node (ref "U8") (pin "2") (pinfunction "-Ctrll_2") (pintype "passive"))
      (node (ref "U9") (pin "2") (pinfunction "-Ctrll_2") (pintype "passive"))
    )
  )
)
